# SCH_NFC-Card-Kristen_2024-10-10.net
KiCad netlist of a schematic drawn in EasyEDA
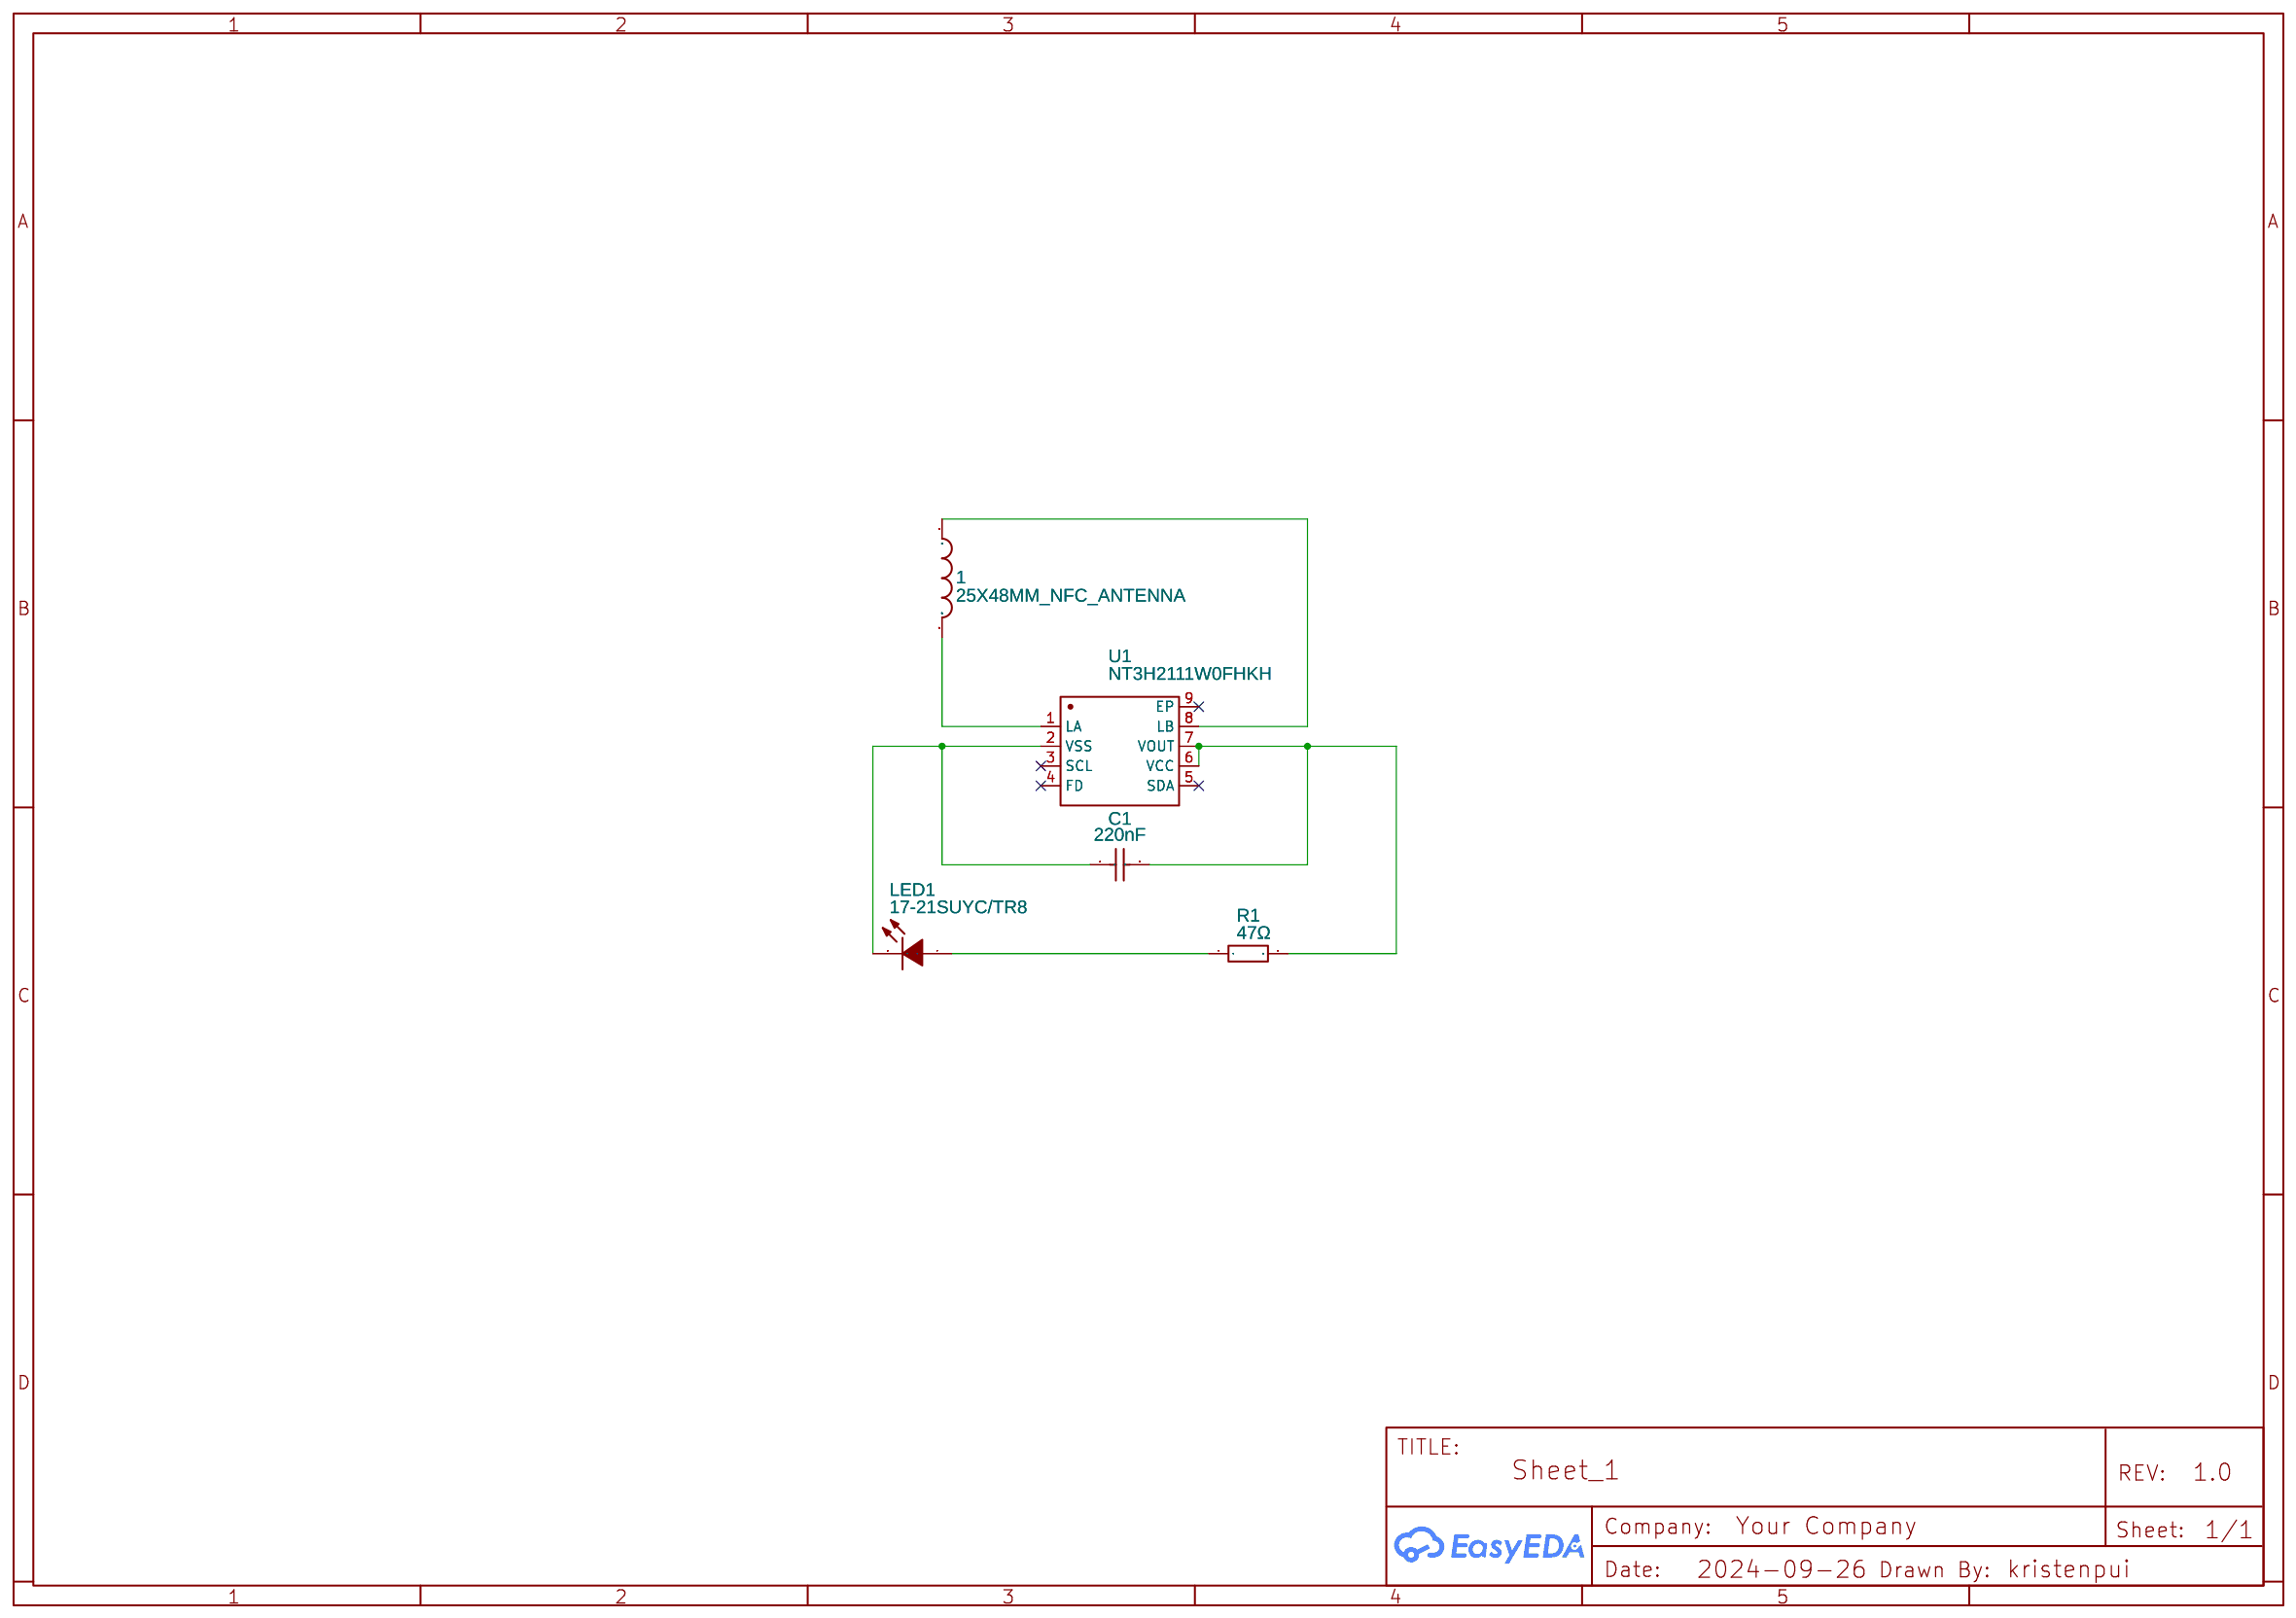
[diagram p0: schematic sheet]

(export (version "E")
  (design (tool "Eeschema 10.0.6"))
  (components
    (comp (ref "1") (value "25X48MM_NFC_ANTENNA") (libsource (lib "") (part "25X48MM_NFC_ANTENNA")))
    (comp (ref "C1")
      (value "220nF")
      (fields
        (field (name "Manufacturer Part") "CL10B224KA8NNNC")
        (field (name "Manufacturer") "SAMSUNG(三星)")
      )
      (libsource (lib "") (part "CL10B224KA8NNNC"))
    )
    (comp (ref "LED1")
      (value "17-21SUYC/TR8")
      (fields (field (name "Manufacturer Part") "KT-0805黄灯") (field (name "Manufacturer") "KENTO"))
      (libsource (lib "") (part "17-21SUYC/TR8"))
    )
    (comp (ref "R1")
      (value "47Ω")
      (fields
        (field (name "Manufacturer Part") "0603WAF470JT5E")
        (field (name "Manufacturer") "UNI-ROYAL(厚声)")
      )
      (libsource (lib "") (part "0603WAF470JT5E"))
    )
    (comp (ref "U1")
      (value "NT3H2111W0FHKH")
      (fields (field (name "Manufacturer") "NXP(恩智浦)"))
      (libsource (lib "") (part "NT3H2111W0FHKH"))
    )
  )
  (nets
    (net (code "1") (name "Net-(LED1-+)") (class "Default")
      (node (ref "LED1") (pin "1") (pinfunction "+_1") (pintype "unspecified"))
      (node (ref "R1") (pin "1") (pinfunction "1_1") (pintype "input"))
    )
    (net (code "2") (name "Net-(LED1--)") (class "Default")
      (node (ref "C1") (pin "1") (pinfunction "1_1") (pintype "input"))
      (node (ref "LED1") (pin "2") (pinfunction "-_2") (pintype "unspecified"))
      (node (ref "U1") (pin "2") (pinfunction "VSS_2") (pintype "unspecified"))
    )
    (net (code "3") (name "Net-(U1-LA)") (class "Default")
      (node (ref "1") (pin "P$2") (pinfunction "P$2_P$2") (pintype "bidirectional"))
      (node (ref "U1") (pin "1") (pinfunction "LA_1") (pintype "unspecified"))
    )
    (net (code "4") (name "Net-(U1-LB)") (class "Default")
      (node (ref "1") (pin "P$1") (pinfunction "P$1_P$1") (pintype "bidirectional"))
      (node (ref "U1") (pin "8") (pinfunction "LB_8") (pintype "unspecified"))
    )
    (net (code "5") (name "Net-(U1-VCC)") (class "Default")
      (node (ref "C1") (pin "2") (pinfunction "2_2") (pintype "input"))
      (node (ref "R1") (pin "2") (pinfunction "2_2") (pintype "input"))
      (node (ref "U1") (pin "6") (pinfunction "VCC_6") (pintype "unspecified"))
      (node (ref "U1") (pin "7") (pinfunction "VOUT_7") (pintype "unspecified"))
    )
    (net (code "6") (name "unconnected-(U1-EP-Pad9)") (class "Default")
      (node (ref "U1") (pin "9") (pinfunction "EP_9") (pintype "unspecified+no_connect"))
    )
    (net (code "7") (name "unconnected-(U1-FD-Pad4)") (class "Default")
      (node (ref "U1") (pin "4") (pinfunction "FD_4") (pintype "unspecified+no_connect"))
    )
    (net (code "8") (name "unconnected-(U1-SCL-Pad3)") (class "Default")
      (node (ref "U1") (pin "3") (pinfunction "SCL_3") (pintype "unspecified+no_connect"))
    )
    (net (code "9") (name "unconnected-(U1-SDA-Pad5)") (class "Default")
      (node (ref "U1") (pin "5") (pinfunction "SDA_5") (pintype "unspecified+no_connect"))
    )
  )
)
